# Track_Me.net
KiCad netlist of a schematic drawn in EAGLE
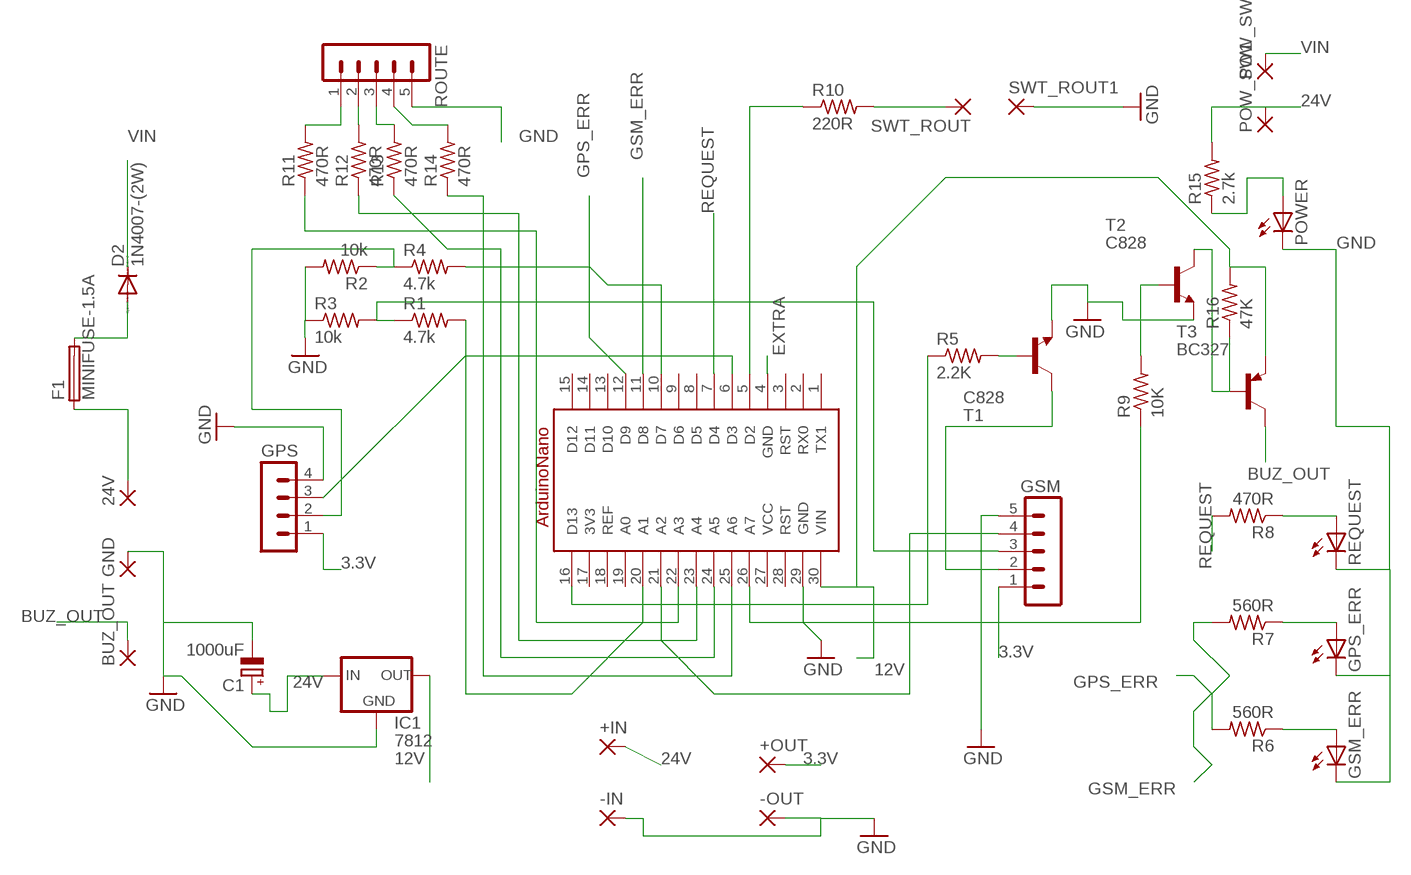
[diagram p0: schematic, sheet 1]

(export (version "E")
  (design (tool "Eeschema 10.0.6"))
  (components
    (comp (ref "+IN")
      (value "3,17/1,3")
      (footprint "eagle-import:3,17_1,3")
      (libsource (lib "eagle-import") (part "3,17/1,3"))
    )
    (comp (ref "+OUT")
      (value "3,17/1,3")
      (footprint "eagle-import:3,17_1,3")
      (libsource (lib "eagle-import") (part "3,17/1,3"))
    )
    (comp (ref "-IN")
      (value "3,17/1,3")
      (footprint "eagle-import:3,17_1,3")
      (libsource (lib "eagle-import") (part "3,17/1,3"))
    )
    (comp (ref "-OUT")
      (value "3,17/1,3")
      (footprint "eagle-import:3,17_1,3")
      (libsource (lib "eagle-import") (part "3,17/1,3"))
    )
    (comp (ref "24V")
      (value "2,54/1,1")
      (footprint "eagle-import:2,54_1,1")
      (libsource (lib "eagle-import") (part "2,54/1,1"))
    )
    (comp (ref "A1")
      (value "ARDUINONANO")
      (footprint "eagle-import:ARDUINONANO")
      (libsource (lib "eagle-import") (part "ARDUINONANO"))
    )
    (comp (ref "BUZ_OUT")
      (value "2,54/1,1")
      (footprint "eagle-import:2,54_1,1")
      (libsource (lib "eagle-import") (part "2,54/1,1"))
    )
    (comp (ref "C1")
      (value "1000uF")
      (footprint "eagle-import:E5-10,5")
      (libsource (lib "eagle-import") (part "CPOL-EUE5-10.5"))
    )
    (comp (ref "D2")
      (value "1N4007-(2W)")
      (footprint "eagle-import:DO35-7")
      (libsource (lib "eagle-import") (part "1N4148DO35-7"))
    )
    (comp (ref "F1")
      (value "MINIFUSE-1.5A")
      (footprint "eagle-import:PICOFUSE")
      (libsource (lib "eagle-import") (part "FUSEPICOFUSE"))
    )
    (comp (ref "GND")
      (value "2,54/1,1")
      (footprint "eagle-import:2,54_1,1")
      (libsource (lib "eagle-import") (part "2,54/1,1"))
    )
    (comp (ref "GPS")
      (value "MA04-1")
      (footprint "eagle-import:MA04-1")
      (libsource (lib "eagle-import") (part "MA04-1"))
    )
    (comp (ref "GPS_ERR")
      (value "LED3MM")
      (footprint "eagle-import:LED3MM")
      (libsource (lib "eagle-import") (part "LED3MM"))
    )
    (comp (ref "GSM")
      (value "MA05-1")
      (footprint "eagle-import:MA05-1")
      (libsource (lib "eagle-import") (part "MA05-1"))
    )
    (comp (ref "GSM_ERR")
      (value "LED3MM")
      (footprint "eagle-import:LED3MM")
      (libsource (lib "eagle-import") (part "LED3MM"))
    )
    (comp (ref "IC1")
      (value "7812")
      (footprint "eagle-import:78MXXS")
      (libsource (lib "eagle-import") (part "78MXXS"))
    )
    (comp (ref "POWER")
      (value "LED3MM")
      (footprint "eagle-import:LED3MM")
      (libsource (lib "eagle-import") (part "LED3MM"))
    )
    (comp (ref "POW_SW")
      (value "2,54/1,1")
      (footprint "eagle-import:2,54_1,1")
      (libsource (lib "eagle-import") (part "2,54/1,1"))
    )
    (comp (ref "POW_SW1")
      (value "2,54/1,1")
      (footprint "eagle-import:2,54_1,1")
      (libsource (lib "eagle-import") (part "2,54/1,1"))
    )
    (comp (ref "R1")
      (value "4.7k")
      (footprint "eagle-import:0207_7")
      (libsource (lib "eagle-import") (part "R-US_0207/7"))
    )
    (comp (ref "R2")
      (value "10k")
      (footprint "eagle-import:0207_7")
      (libsource (lib "eagle-import") (part "R-US_0207/7"))
    )
    (comp (ref "R3")
      (value "10k")
      (footprint "eagle-import:0207_7")
      (libsource (lib "eagle-import") (part "R-US_0207/7"))
    )
    (comp (ref "R4")
      (value "4.7k")
      (footprint "eagle-import:0207_7")
      (libsource (lib "eagle-import") (part "R-US_0207/7"))
    )
    (comp (ref "R5")
      (value "2.2K")
      (footprint "eagle-import:0207_7")
      (libsource (lib "eagle-import") (part "R-US_0207/7"))
    )
    (comp (ref "R6")
      (value "560R")
      (footprint "eagle-import:0207_7")
      (libsource (lib "eagle-import") (part "R-US_0207/7"))
    )
    (comp (ref "R7")
      (value "560R")
      (footprint "eagle-import:0207_7")
      (libsource (lib "eagle-import") (part "R-US_0207/7"))
    )
    (comp (ref "R8")
      (value "470R")
      (footprint "eagle-import:0207_7")
      (libsource (lib "eagle-import") (part "R-US_0207/7"))
    )
    (comp (ref "R9")
      (value "10K")
      (footprint "eagle-import:0207_7")
      (libsource (lib "eagle-import") (part "R-US_0207/7"))
    )
    (comp (ref "R10")
      (value "220R")
      (footprint "eagle-import:0207_7")
      (libsource (lib "eagle-import") (part "R-US_0207/7"))
    )
    (comp (ref "R11")
      (value "470R")
      (footprint "eagle-import:0207_7")
      (libsource (lib "eagle-import") (part "R-US_0207/7"))
    )
    (comp (ref "R12")
      (value "470R")
      (footprint "eagle-import:0207_7")
      (libsource (lib "eagle-import") (part "R-US_0207/7"))
    )
    (comp (ref "R13")
      (value "470R")
      (footprint "eagle-import:0207_7")
      (libsource (lib "eagle-import") (part "R-US_0207/7"))
    )
    (comp (ref "R14")
      (value "470R")
      (footprint "eagle-import:0207_7")
      (libsource (lib "eagle-import") (part "R-US_0207/7"))
    )
    (comp (ref "R15")
      (value "2.7k")
      (footprint "eagle-import:0207_7")
      (libsource (lib "eagle-import") (part "R-US_0207/7"))
    )
    (comp (ref "R16")
      (value "47K")
      (footprint "eagle-import:0207_7")
      (libsource (lib "eagle-import") (part "R-US_0207/7"))
    )
    (comp (ref "REQUEST")
      (value "LED3MM")
      (footprint "eagle-import:LED3MM")
      (libsource (lib "eagle-import") (part "LED3MM"))
    )
    (comp (ref "ROUTE")
      (value "MA05-1")
      (footprint "eagle-import:MA05-1")
      (libsource (lib "eagle-import") (part "MA05-1"))
    )
    (comp (ref "SWT_ROUT")
      (value "2,54/1,1")
      (footprint "eagle-import:2,54_1,1")
      (libsource (lib "eagle-import") (part "2,54/1,1"))
    )
    (comp (ref "SWT_ROUT1")
      (value "2,54/1,1")
      (footprint "eagle-import:2,54_1,1")
      (libsource (lib "eagle-import") (part "2,54/1,1"))
    )
    (comp (ref "T1")
      (value "C828")
      (footprint "eagle-import:TO92-ECB")
      (libsource (lib "eagle-import") (part "2SC945"))
    )
    (comp (ref "T2")
      (value "C828")
      (footprint "eagle-import:TO92-ECB")
      (libsource (lib "eagle-import") (part "2SC945"))
    )
    (comp (ref "T3")
      (value "BC327")
      (footprint "eagle-import:TO92-EBC")
      (libsource (lib "eagle-import") (part "-PNP-TO92-EBCBC327"))
    )
  )
  (nets
    (net (code "1") (name "/3.3V") (class "Default")
      (node (ref "+OUT") (pin "1") (pinfunction "P_1") (pintype "passive"))
      (node (ref "GPS") (pin "1") (pinfunction "1_1") (pintype "passive"))
      (node (ref "GSM") (pin "1") (pinfunction "1_1") (pintype "passive"))
    )
    (net (code "2") (name "/3V3") (class "Default")
      (node (ref "A1") (pin "17") (pinfunction "3V3_17") (pintype "power_in"))
    )
    (net (code "3") (name "/12V") (class "Default")
      (node (ref "A1") (pin "30") (pinfunction "VIN_30") (pintype "power_in"))
      (node (ref "IC1") (pin "OUT") (pinfunction "OUT_OUT") (pintype "passive"))
      (node (ref "R16") (pin "2") (pinfunction "2_2") (pintype "passive"))
      (node (ref "T3") (pin "E") (pinfunction "E_E") (pintype "passive"))
    )
    (net (code "4") (name "/24V") (class "Default")
      (node (ref "+IN") (pin "1") (pinfunction "P_1") (pintype "passive"))
      (node (ref "C1") (pin "+") (pinfunction "+_+") (pintype "passive"))
      (node (ref "IC1") (pin "IN") (pinfunction "IN_IN") (pintype "input"))
      (node (ref "POW_SW1") (pin "1") (pinfunction "P_1") (pintype "passive"))
      (node (ref "R15") (pin "2") (pinfunction "2_2") (pintype "passive"))
    )
    (net (code "5") (name "/BUZ_OUT") (class "Default")
      (node (ref "BUZ_OUT") (pin "1") (pinfunction "P_1") (pintype "passive"))
      (node (ref "T3") (pin "C") (pinfunction "C_C") (pintype "passive"))
    )
    (net (code "6") (name "/EXTRA") (class "Default")
      (node (ref "A1") (pin "4") (pinfunction "GND_4") (pintype "power_in"))
    )
    (net (code "7") (name "/GPS_ERR") (class "Default")
      (node (ref "A1") (pin "12") (pinfunction "D9_12") (pintype "output"))
      (node (ref "R6") (pin "2") (pinfunction "2_2") (pintype "passive"))
    )
    (net (code "8") (name "/GSM_ERR") (class "Default")
      (node (ref "A1") (pin "11") (pinfunction "D8_11") (pintype "output"))
      (node (ref "R7") (pin "2") (pinfunction "2_2") (pintype "passive"))
    )
    (net (code "9") (name "/REF") (class "Default")
      (node (ref "A1") (pin "18") (pinfunction "REF_18") (pintype "power_in"))
    )
    (net (code "10") (name "/REQUEST") (class "Default")
      (node (ref "A1") (pin "7") (pinfunction "D4_7") (pintype "output"))
      (node (ref "R8") (pin "2") (pinfunction "2_2") (pintype "passive"))
    )
    (net (code "11") (name "/VCC") (class "Default")
      (node (ref "A1") (pin "27") (pinfunction "VCC_27") (pintype "power_in"))
    )
    (net (code "12") (name "/VIN") (class "Default")
      (node (ref "D2") (pin "C") (pinfunction "C_C") (pintype "passive"))
      (node (ref "POW_SW") (pin "1") (pinfunction "P_1") (pintype "passive"))
    )
    (net (code "13") (name "GND") (class "Default")
      (node (ref "-IN") (pin "1") (pinfunction "P_1") (pintype "passive"))
      (node (ref "-OUT") (pin "1") (pinfunction "P_1") (pintype "passive"))
      (node (ref "A1") (pin "29") (pinfunction "GND_29") (pintype "power_in"))
      (node (ref "C1") (pin "-") (pinfunction "-_-") (pintype "passive"))
      (node (ref "GND") (pin "1") (pinfunction "P_1") (pintype "passive"))
      (node (ref "GPS") (pin "4") (pinfunction "4_4") (pintype "passive"))
      (node (ref "GPS_ERR") (pin "K") (pinfunction "C_K") (pintype "passive"))
      (node (ref "GSM") (pin "5") (pinfunction "5_5") (pintype "passive"))
      (node (ref "GSM_ERR") (pin "K") (pinfunction "C_K") (pintype "passive"))
      (node (ref "IC1") (pin "GND") (pinfunction "GND_GND") (pintype "input"))
      (node (ref "POWER") (pin "K") (pinfunction "C_K") (pintype "passive"))
      (node (ref "R2") (pin "2") (pinfunction "2_2") (pintype "passive"))
      (node (ref "R3") (pin "1") (pinfunction "1_1") (pintype "passive"))
      (node (ref "REQUEST") (pin "K") (pinfunction "C_K") (pintype "passive"))
      (node (ref "ROUTE") (pin "5") (pinfunction "5_5") (pintype "passive"))
      (node (ref "SWT_ROUT1") (pin "1") (pinfunction "P_1") (pintype "passive"))
      (node (ref "T1") (pin "E") (pinfunction "E_E") (pintype "passive"))
      (node (ref "T2") (pin "E") (pinfunction "E_E") (pintype "passive"))
    )
    (net (code "14") (name "Net-(24V-P)") (class "Default")
      (node (ref "24V") (pin "1") (pinfunction "P_1") (pintype "passive"))
      (node (ref "F1") (pin "1") (pinfunction "1_1") (pintype "passive"))
    )
    (net (code "15") (name "Net-(A1-A1)") (class "Default")
      (node (ref "A1") (pin "20") (pinfunction "A1_20") (pintype "input"))
      (node (ref "R1") (pin "2") (pinfunction "2_2") (pintype "passive"))
    )
    (net (code "16") (name "Net-(A1-A2)") (class "Default")
      (node (ref "A1") (pin "21") (pinfunction "A2_21") (pintype "input"))
      (node (ref "GSM") (pin "4") (pinfunction "4_4") (pintype "passive"))
    )
    (net (code "17") (name "Net-(A1-A3)") (class "Default")
      (node (ref "A1") (pin "22") (pinfunction "A3_22") (pintype "input"))
      (node (ref "R11") (pin "1") (pinfunction "1_1") (pintype "passive"))
    )
    (net (code "18") (name "Net-(A1-A4)") (class "Default")
      (node (ref "A1") (pin "23") (pinfunction "A4_23") (pintype "input"))
      (node (ref "R12") (pin "1") (pinfunction "1_1") (pintype "passive"))
    )
    (net (code "19") (name "Net-(A1-A5)") (class "Default")
      (node (ref "A1") (pin "24") (pinfunction "A5_24") (pintype "input"))
      (node (ref "R13") (pin "1") (pinfunction "1_1") (pintype "passive"))
    )
    (net (code "20") (name "Net-(A1-A6)") (class "Default")
      (node (ref "A1") (pin "25") (pinfunction "A6_25") (pintype "input"))
      (node (ref "R14") (pin "1") (pinfunction "1_1") (pintype "passive"))
    )
    (net (code "21") (name "Net-(A1-A7)") (class "Default")
      (node (ref "A1") (pin "26") (pinfunction "A7_26") (pintype "input"))
      (node (ref "R9") (pin "1") (pinfunction "1_1") (pintype "passive"))
    )
    (net (code "22") (name "Net-(A1-D2)") (class "Default")
      (node (ref "A1") (pin "5") (pinfunction "D2_5") (pintype "output"))
      (node (ref "R10") (pin "1") (pinfunction "1_1") (pintype "passive"))
    )
    (net (code "23") (name "Net-(A1-D3)") (class "Default")
      (node (ref "A1") (pin "6") (pinfunction "D3_6") (pintype "output"))
      (node (ref "GPS") (pin "3") (pinfunction "3_3") (pintype "passive"))
    )
    (net (code "24") (name "Net-(A1-D7)") (class "Default")
      (node (ref "A1") (pin "10") (pinfunction "D7_10") (pintype "output"))
      (node (ref "R4") (pin "2") (pinfunction "2_2") (pintype "passive"))
    )
    (net (code "25") (name "Net-(A1-D13)") (class "Default")
      (node (ref "A1") (pin "16") (pinfunction "D13_16") (pintype "output"))
      (node (ref "R5") (pin "1") (pinfunction "1_1") (pintype "passive"))
    )
    (net (code "26") (name "Net-(D2-PadA)") (class "Default")
      (node (ref "D2") (pin "A") (pinfunction "A_A") (pintype "passive"))
      (node (ref "F1") (pin "2") (pinfunction "2_2") (pintype "passive"))
    )
    (net (code "27") (name "Net-(GPS-Pad2)") (class "Default")
      (node (ref "GPS") (pin "2") (pinfunction "2_2") (pintype "passive"))
      (node (ref "R2") (pin "1") (pinfunction "1_1") (pintype "passive"))
      (node (ref "R4") (pin "1") (pinfunction "1_1") (pintype "passive"))
    )
    (net (code "28") (name "Net-(GPS_ERR-PadA)") (class "Default")
      (node (ref "GPS_ERR") (pin "A") (pinfunction "A_A") (pintype "passive"))
      (node (ref "R7") (pin "1") (pinfunction "1_1") (pintype "passive"))
    )
    (net (code "29") (name "Net-(GSM-Pad2)") (class "Default")
      (node (ref "GSM") (pin "2") (pinfunction "2_2") (pintype "passive"))
      (node (ref "T1") (pin "C") (pinfunction "C_C") (pintype "passive"))
    )
    (net (code "30") (name "Net-(GSM-Pad3)") (class "Default")
      (node (ref "GSM") (pin "3") (pinfunction "3_3") (pintype "passive"))
      (node (ref "R1") (pin "1") (pinfunction "1_1") (pintype "passive"))
      (node (ref "R3") (pin "2") (pinfunction "2_2") (pintype "passive"))
    )
    (net (code "31") (name "Net-(GSM_ERR-PadA)") (class "Default")
      (node (ref "GSM_ERR") (pin "A") (pinfunction "A_A") (pintype "passive"))
      (node (ref "R6") (pin "1") (pinfunction "1_1") (pintype "passive"))
    )
    (net (code "32") (name "Net-(POWER-PadA)") (class "Default")
      (node (ref "POWER") (pin "A") (pinfunction "A_A") (pintype "passive"))
      (node (ref "R15") (pin "1") (pinfunction "1_1") (pintype "passive"))
    )
    (net (code "33") (name "Net-(R5-Pad2)") (class "Default")
      (node (ref "R5") (pin "2") (pinfunction "2_2") (pintype "passive"))
      (node (ref "T1") (pin "B") (pinfunction "B_B") (pintype "passive"))
    )
    (net (code "34") (name "Net-(R8-Pad1)") (class "Default")
      (node (ref "R8") (pin "1") (pinfunction "1_1") (pintype "passive"))
      (node (ref "REQUEST") (pin "A") (pinfunction "A_A") (pintype "passive"))
    )
    (net (code "35") (name "Net-(R9-Pad2)") (class "Default")
      (node (ref "R9") (pin "2") (pinfunction "2_2") (pintype "passive"))
      (node (ref "T2") (pin "B") (pinfunction "B_B") (pintype "passive"))
    )
    (net (code "36") (name "Net-(R11-Pad2)") (class "Default")
      (node (ref "R11") (pin "2") (pinfunction "2_2") (pintype "passive"))
      (node (ref "ROUTE") (pin "1") (pinfunction "1_1") (pintype "passive"))
    )
    (net (code "37") (name "Net-(R12-Pad2)") (class "Default")
      (node (ref "R12") (pin "2") (pinfunction "2_2") (pintype "passive"))
      (node (ref "ROUTE") (pin "2") (pinfunction "2_2") (pintype "passive"))
    )
    (net (code "38") (name "Net-(R13-Pad2)") (class "Default")
      (node (ref "R13") (pin "2") (pinfunction "2_2") (pintype "passive"))
      (node (ref "ROUTE") (pin "3") (pinfunction "3_3") (pintype "passive"))
    )
    (net (code "39") (name "Net-(R14-Pad2)") (class "Default")
      (node (ref "R14") (pin "2") (pinfunction "2_2") (pintype "passive"))
      (node (ref "ROUTE") (pin "4") (pinfunction "4_4") (pintype "passive"))
    )
    (net (code "40") (name "Net-(R16-Pad1)") (class "Default")
      (node (ref "R16") (pin "1") (pinfunction "1_1") (pintype "passive"))
      (node (ref "T2") (pin "C") (pinfunction "C_C") (pintype "passive"))
      (node (ref "T3") (pin "B") (pinfunction "B_B") (pintype "passive"))
    )
    (net (code "41") (name "Net-(SWT_ROUT-P)") (class "Default")
      (node (ref "R10") (pin "2") (pinfunction "2_2") (pintype "passive"))
      (node (ref "SWT_ROUT") (pin "1") (pinfunction "P_1") (pintype "passive"))
    )
    (net (code "42") (name "unconnected-(A1-A0-Pad19)") (class "Default")
      (node (ref "A1") (pin "19") (pinfunction "A0_19") (pintype "input"))
    )
    (net (code "43") (name "unconnected-(A1-D5-Pad8)") (class "Default")
      (node (ref "A1") (pin "8") (pinfunction "D5_8") (pintype "output"))
    )
    (net (code "44") (name "unconnected-(A1-D6-Pad9)") (class "Default")
      (node (ref "A1") (pin "9") (pinfunction "D6_9") (pintype "output"))
    )
    (net (code "45") (name "unconnected-(A1-D10-Pad13)") (class "Default")
      (node (ref "A1") (pin "13") (pinfunction "D10_13") (pintype "output"))
    )
    (net (code "46") (name "unconnected-(A1-D11-Pad14)") (class "Default")
      (node (ref "A1") (pin "14") (pinfunction "D11_14") (pintype "output"))
    )
    (net (code "47") (name "unconnected-(A1-D12-Pad15)") (class "Default")
      (node (ref "A1") (pin "15") (pinfunction "D12_15") (pintype "output"))
    )
    (net (code "48") (name "unconnected-(A1-RST-Pad3)") (class "Default")
      (node (ref "A1") (pin "3") (pinfunction "RST_3") (pintype "input"))
    )
    (net (code "49") (name "unconnected-(A1-RST-Pad28)") (class "Default")
      (node (ref "A1") (pin "28") (pinfunction "RST_28") (pintype "input"))
    )
    (net (code "50") (name "unconnected-(A1-RX0-Pad2)") (class "Default")
      (node (ref "A1") (pin "2") (pinfunction "RX0_2") (pintype "bidirectional"))
    )
    (net (code "51") (name "unconnected-(A1-TX1-Pad1)") (class "Default")
      (node (ref "A1") (pin "1") (pinfunction "TX1_1") (pintype "bidirectional"))
    )
  )
)
